# GMSL_DESERIALIZER.net
KiCad netlist of a schematic drawn in Altium Designer
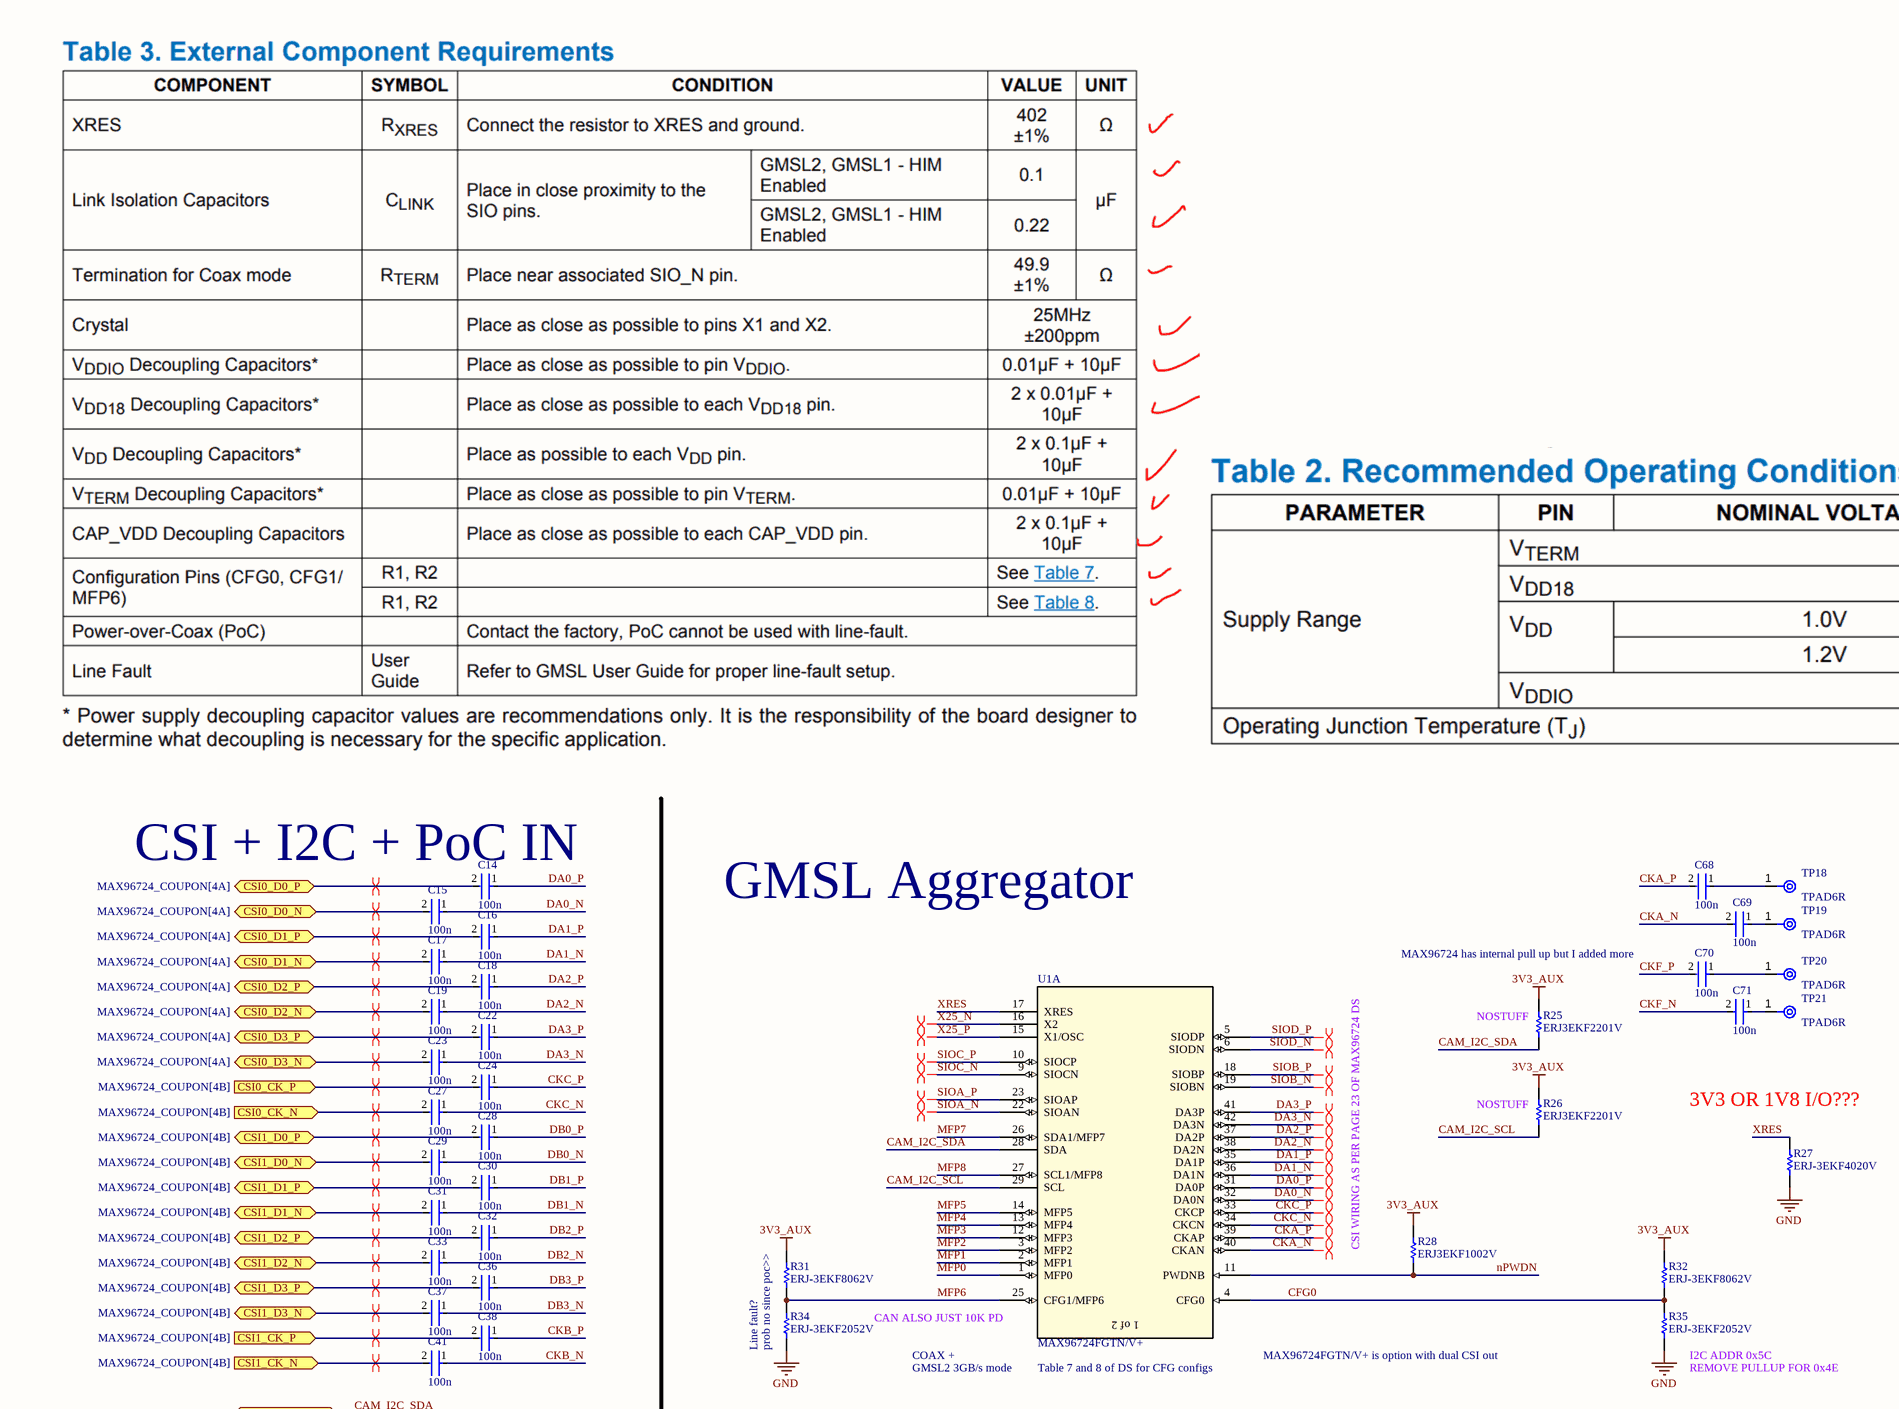
[diagram p0: GMSL_DESERIALIZER.SchDoc, top left]
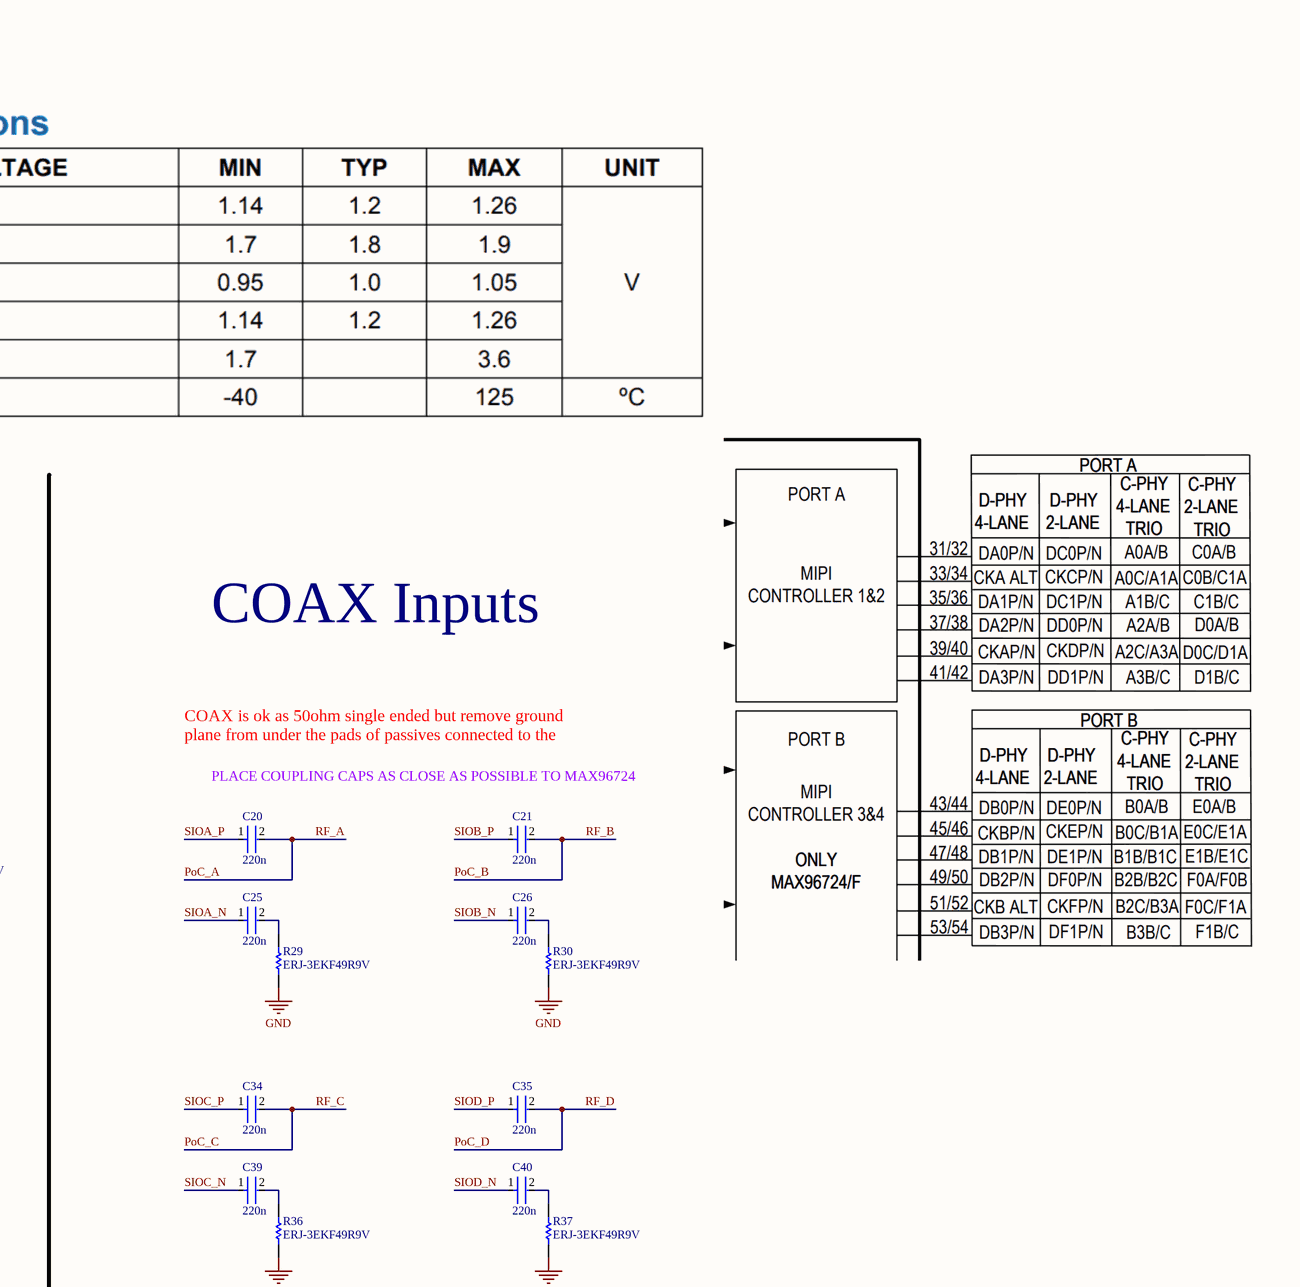
[diagram p1: GMSL_DESERIALIZER.SchDoc, top right]
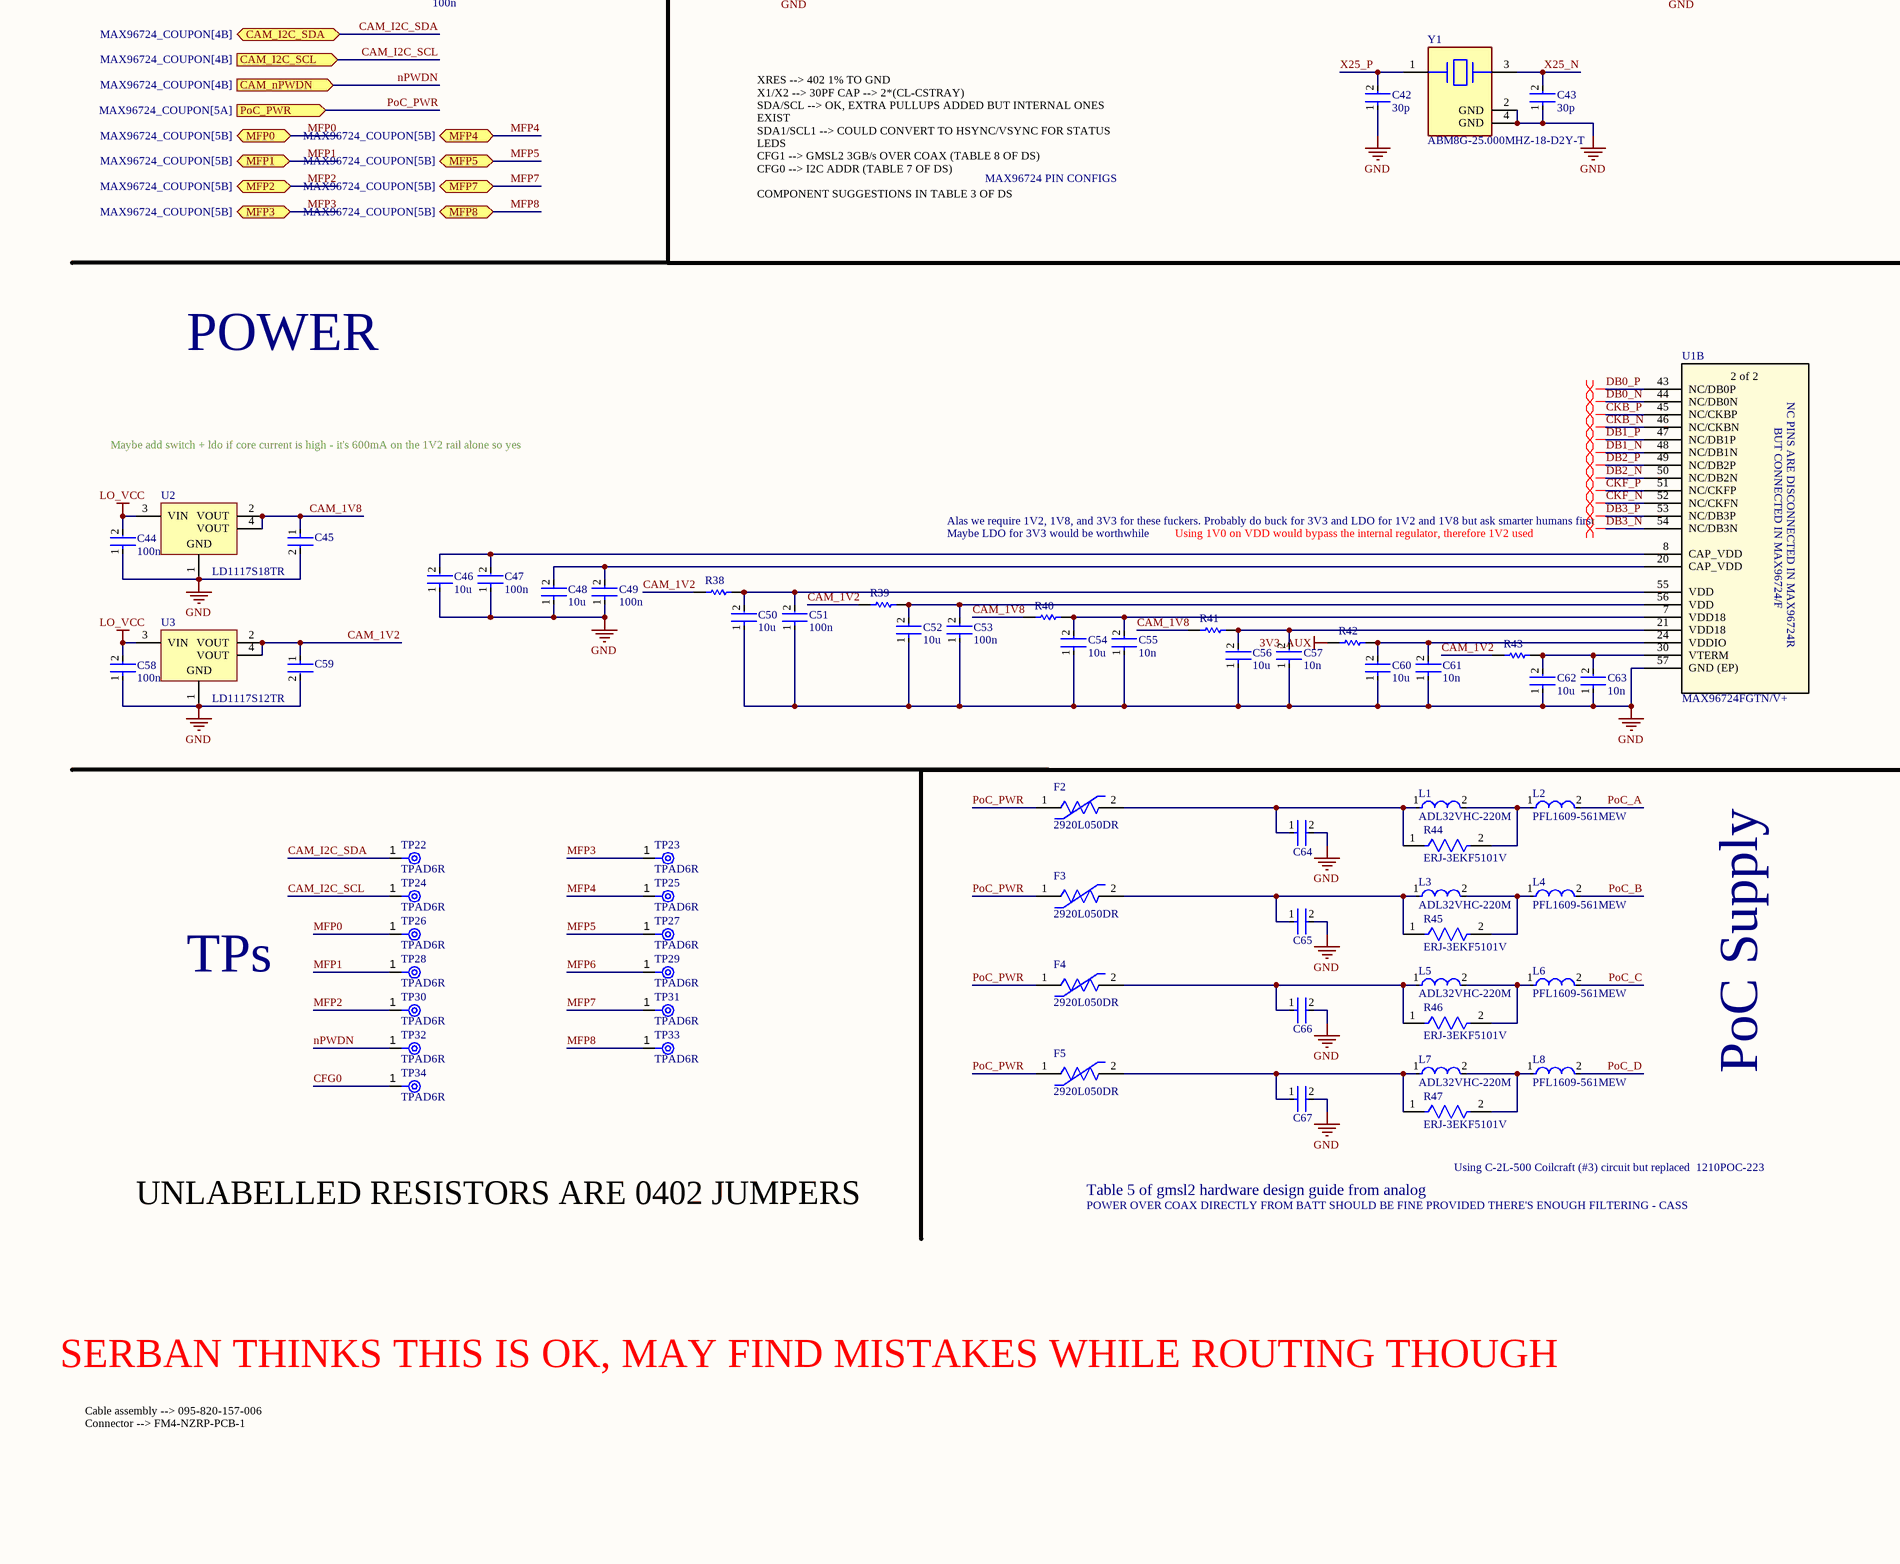
[diagram p2: GMSL_DESERIALIZER.SchDoc, bottom left]
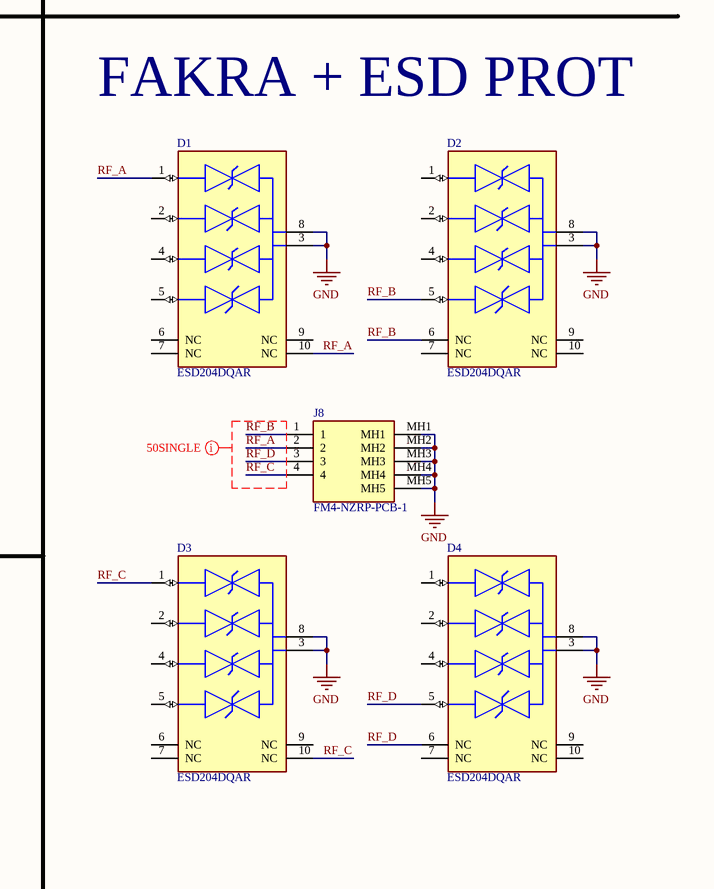
[diagram p3: GMSL_DESERIALIZER.SchDoc, bottom right]

(export (version "E")
  (design (tool "Eeschema 10.0.6"))
  (components
    (comp (ref "C14")
      (value "100n")
      (footprint "FP-0402-L_1_0_0_05-W_0_5-IPC_A")
      (description "LARGE PADS, 0402 CAP, CHANGE COMMENT TO MATCH REAL P/N")
      (libsource (lib "Space Concordia") (part "b4654b650e69147ec39a6b967a45e02"))
    )
    (comp (ref "C15")
      (value "100n")
      (footprint "FP-0402-L_1_0_0_05-W_0_5-IPC_A")
      (description "LARGE PADS, 0402 CAP, CHANGE COMMENT TO MATCH REAL P/N")
      (libsource (lib "Space Concordia") (part "b4654b650e69147ec39a6b967a45e02"))
    )
    (comp (ref "C16")
      (value "100n")
      (footprint "FP-0402-L_1_0_0_05-W_0_5-IPC_A")
      (description "LARGE PADS, 0402 CAP, CHANGE COMMENT TO MATCH REAL P/N")
      (libsource (lib "Space Concordia") (part "b4654b650e69147ec39a6b967a45e02"))
    )
    (comp (ref "C17")
      (value "100n")
      (footprint "FP-0402-L_1_0_0_05-W_0_5-IPC_A")
      (description "LARGE PADS, 0402 CAP, CHANGE COMMENT TO MATCH REAL P/N")
      (libsource (lib "Space Concordia") (part "b4654b650e69147ec39a6b967a45e02"))
    )
    (comp (ref "C18")
      (value "100n")
      (footprint "FP-0402-L_1_0_0_05-W_0_5-IPC_A")
      (description "LARGE PADS, 0402 CAP, CHANGE COMMENT TO MATCH REAL P/N")
      (libsource (lib "Space Concordia") (part "b4654b650e69147ec39a6b967a45e02"))
    )
    (comp (ref "C19")
      (value "100n")
      (footprint "FP-0402-L_1_0_0_05-W_0_5-IPC_A")
      (description "LARGE PADS, 0402 CAP, CHANGE COMMENT TO MATCH REAL P/N")
      (libsource (lib "Space Concordia") (part "b4654b650e69147ec39a6b967a45e02"))
    )
    (comp (ref "C20")
      (value "220n")
      (footprint "FP-0402-L_1_0_0_05-W_0_5-IPC_A")
      (description "LARGE PADS, 0402 CAP, CHANGE COMMENT TO MATCH REAL P/N")
      (libsource (lib "Space Concordia") (part "b4654b650e69147ec39a6b967a45e02"))
    )
    (comp (ref "C21")
      (value "220n")
      (footprint "FP-0402-L_1_0_0_05-W_0_5-IPC_A")
      (description "LARGE PADS, 0402 CAP, CHANGE COMMENT TO MATCH REAL P/N")
      (libsource (lib "Space Concordia") (part "b4654b650e69147ec39a6b967a45e02"))
    )
    (comp (ref "C22")
      (value "100n")
      (footprint "FP-0402-L_1_0_0_05-W_0_5-IPC_A")
      (description "LARGE PADS, 0402 CAP, CHANGE COMMENT TO MATCH REAL P/N")
      (libsource (lib "Space Concordia") (part "b4654b650e69147ec39a6b967a45e02"))
    )
    (comp (ref "C23")
      (value "100n")
      (footprint "FP-0402-L_1_0_0_05-W_0_5-IPC_A")
      (description "LARGE PADS, 0402 CAP, CHANGE COMMENT TO MATCH REAL P/N")
      (libsource (lib "Space Concordia") (part "b4654b650e69147ec39a6b967a45e02"))
    )
    (comp (ref "C24")
      (value "100n")
      (footprint "FP-0402-L_1_0_0_05-W_0_5-IPC_A")
      (description "LARGE PADS, 0402 CAP, CHANGE COMMENT TO MATCH REAL P/N")
      (libsource (lib "Space Concordia") (part "b4654b650e69147ec39a6b967a45e02"))
    )
    (comp (ref "C25")
      (value "220n")
      (footprint "FP-0402-L_1_0_0_05-W_0_5-IPC_A")
      (description "LARGE PADS, 0402 CAP, CHANGE COMMENT TO MATCH REAL P/N")
      (libsource (lib "Space Concordia") (part "b4654b650e69147ec39a6b967a45e02"))
    )
    (comp (ref "C26")
      (value "220n")
      (footprint "FP-0402-L_1_0_0_05-W_0_5-IPC_A")
      (description "LARGE PADS, 0402 CAP, CHANGE COMMENT TO MATCH REAL P/N")
      (libsource (lib "Space Concordia") (part "b4654b650e69147ec39a6b967a45e02"))
    )
    (comp (ref "C27")
      (value "100n")
      (footprint "FP-0402-L_1_0_0_05-W_0_5-IPC_A")
      (description "LARGE PADS, 0402 CAP, CHANGE COMMENT TO MATCH REAL P/N")
      (libsource (lib "Space Concordia") (part "b4654b650e69147ec39a6b967a45e02"))
    )
    (comp (ref "C28")
      (value "100n")
      (footprint "FP-0402-L_1_0_0_05-W_0_5-IPC_A")
      (description "LARGE PADS, 0402 CAP, CHANGE COMMENT TO MATCH REAL P/N")
      (libsource (lib "Space Concordia") (part "b4654b650e69147ec39a6b967a45e02"))
    )
    (comp (ref "C29")
      (value "100n")
      (footprint "FP-0402-L_1_0_0_05-W_0_5-IPC_A")
      (description "LARGE PADS, 0402 CAP, CHANGE COMMENT TO MATCH REAL P/N")
      (libsource (lib "Space Concordia") (part "b4654b650e69147ec39a6b967a45e02"))
    )
    (comp (ref "C30")
      (value "100n")
      (footprint "FP-0402-L_1_0_0_05-W_0_5-IPC_A")
      (description "LARGE PADS, 0402 CAP, CHANGE COMMENT TO MATCH REAL P/N")
      (libsource (lib "Space Concordia") (part "b4654b650e69147ec39a6b967a45e02"))
    )
    (comp (ref "C31")
      (value "100n")
      (footprint "FP-0402-L_1_0_0_05-W_0_5-IPC_A")
      (description "LARGE PADS, 0402 CAP, CHANGE COMMENT TO MATCH REAL P/N")
      (libsource (lib "Space Concordia") (part "b4654b650e69147ec39a6b967a45e02"))
    )
    (comp (ref "C32")
      (value "100n")
      (footprint "FP-0402-L_1_0_0_05-W_0_5-IPC_A")
      (description "LARGE PADS, 0402 CAP, CHANGE COMMENT TO MATCH REAL P/N")
      (libsource (lib "Space Concordia") (part "b4654b650e69147ec39a6b967a45e02"))
    )
    (comp (ref "C33")
      (value "100n")
      (footprint "FP-0402-L_1_0_0_05-W_0_5-IPC_A")
      (description "LARGE PADS, 0402 CAP, CHANGE COMMENT TO MATCH REAL P/N")
      (libsource (lib "Space Concordia") (part "b4654b650e69147ec39a6b967a45e02"))
    )
    (comp (ref "C34")
      (value "220n")
      (footprint "FP-0402-L_1_0_0_05-W_0_5-IPC_A")
      (description "LARGE PADS, 0402 CAP, CHANGE COMMENT TO MATCH REAL P/N")
      (libsource (lib "Space Concordia") (part "b4654b650e69147ec39a6b967a45e02"))
    )
    (comp (ref "C35")
      (value "220n")
      (footprint "FP-0402-L_1_0_0_05-W_0_5-IPC_A")
      (description "LARGE PADS, 0402 CAP, CHANGE COMMENT TO MATCH REAL P/N")
      (libsource (lib "Space Concordia") (part "b4654b650e69147ec39a6b967a45e02"))
    )
    (comp (ref "C36")
      (value "100n")
      (footprint "FP-0402-L_1_0_0_05-W_0_5-IPC_A")
      (description "LARGE PADS, 0402 CAP, CHANGE COMMENT TO MATCH REAL P/N")
      (libsource (lib "Space Concordia") (part "b4654b650e69147ec39a6b967a45e02"))
    )
    (comp (ref "C37")
      (value "100n")
      (footprint "FP-0402-L_1_0_0_05-W_0_5-IPC_A")
      (description "LARGE PADS, 0402 CAP, CHANGE COMMENT TO MATCH REAL P/N")
      (libsource (lib "Space Concordia") (part "b4654b650e69147ec39a6b967a45e02"))
    )
    (comp (ref "C38")
      (value "100n")
      (footprint "FP-0402-L_1_0_0_05-W_0_5-IPC_A")
      (description "LARGE PADS, 0402 CAP, CHANGE COMMENT TO MATCH REAL P/N")
      (libsource (lib "Space Concordia") (part "b4654b650e69147ec39a6b967a45e02"))
    )
    (comp (ref "C39")
      (value "220n")
      (footprint "FP-0402-L_1_0_0_05-W_0_5-IPC_A")
      (description "LARGE PADS, 0402 CAP, CHANGE COMMENT TO MATCH REAL P/N")
      (libsource (lib "Space Concordia") (part "b4654b650e69147ec39a6b967a45e02"))
    )
    (comp (ref "C40")
      (value "220n")
      (footprint "FP-0402-L_1_0_0_05-W_0_5-IPC_A")
      (description "LARGE PADS, 0402 CAP, CHANGE COMMENT TO MATCH REAL P/N")
      (libsource (lib "Space Concordia") (part "b4654b650e69147ec39a6b967a45e02"))
    )
    (comp (ref "C41")
      (value "100n")
      (footprint "FP-0402-L_1_0_0_05-W_0_5-IPC_A")
      (description "LARGE PADS, 0402 CAP, CHANGE COMMENT TO MATCH REAL P/N")
      (libsource (lib "Space Concordia") (part "b4654b650e69147ec39a6b967a45e02"))
    )
    (comp (ref "C42")
      (value "30p")
      (footprint "FP-0402-L_1_0_0_05-W_0_5-IPC_A")
      (description "LARGE PADS, 0402 CAP, CHANGE COMMENT TO MATCH REAL P/N")
      (libsource (lib "Space Concordia") (part "b4654b650e69147ec39a6b967a45e02"))
    )
    (comp (ref "C43")
      (value "30p")
      (footprint "FP-0402-L_1_0_0_05-W_0_5-IPC_A")
      (description "LARGE PADS, 0402 CAP, CHANGE COMMENT TO MATCH REAL P/N")
      (libsource (lib "Space Concordia") (part "b4654b650e69147ec39a6b967a45e02"))
    )
    (comp (ref "C44")
      (value "100n")
      (footprint "FP-0402-L_1_0_0_05-W_0_5-IPC_A")
      (description "LARGE PADS, 0402 CAP, CHANGE COMMENT TO MATCH REAL P/N")
      (libsource (lib "Space Concordia") (part "b4654b650e69147ec39a6b967a45e02"))
    )
    (comp (ref "C45")
      (value "GRM188R60J106ME47D")
      (footprint "FP-GRM188-0_1-e0_2_0_55-IPC_A")
      (description "Chip Multilayer Ceramic Capacitors for General Purpose, 0603, 10uF, X5R, 15%, 20%, 6.3V")
      (fields (field (name "VOLTAGE") "6.3V") (field (name "TOLERANCE") "20%"))
      (libsource (lib "Altium Content Vault") (part "02cd4be3c70576c341d710602a673aa"))
    )
    (comp (ref "C46")
      (value "10u")
      (footprint "FP-0402-L_1_0_0_05-W_0_5-IPC_A")
      (description "LARGE PADS, 0402 CAP, CHANGE COMMENT TO MATCH REAL P/N")
      (libsource (lib "Space Concordia") (part "b4654b650e69147ec39a6b967a45e02"))
    )
    (comp (ref "C47")
      (value "100n")
      (footprint "FP-0402-L_1_0_0_05-W_0_5-IPC_A")
      (description "LARGE PADS, 0402 CAP, CHANGE COMMENT TO MATCH REAL P/N")
      (libsource (lib "Space Concordia") (part "b4654b650e69147ec39a6b967a45e02"))
    )
    (comp (ref "C48")
      (value "10u")
      (footprint "FP-0402-L_1_0_0_05-W_0_5-IPC_A")
      (description "LARGE PADS, 0402 CAP, CHANGE COMMENT TO MATCH REAL P/N")
      (libsource (lib "Space Concordia") (part "b4654b650e69147ec39a6b967a45e02"))
    )
    (comp (ref "C49")
      (value "100n")
      (footprint "FP-0402-L_1_0_0_05-W_0_5-IPC_A")
      (description "LARGE PADS, 0402 CAP, CHANGE COMMENT TO MATCH REAL P/N")
      (libsource (lib "Space Concordia") (part "b4654b650e69147ec39a6b967a45e02"))
    )
    (comp (ref "C50")
      (value "10u")
      (footprint "FP-0402-L_1_0_0_05-W_0_5-IPC_A")
      (description "LARGE PADS, 0402 CAP, CHANGE COMMENT TO MATCH REAL P/N")
      (libsource (lib "Space Concordia") (part "b4654b650e69147ec39a6b967a45e02"))
    )
    (comp (ref "C51")
      (value "100n")
      (footprint "FP-0402-L_1_0_0_05-W_0_5-IPC_A")
      (description "LARGE PADS, 0402 CAP, CHANGE COMMENT TO MATCH REAL P/N")
      (libsource (lib "Space Concordia") (part "b4654b650e69147ec39a6b967a45e02"))
    )
    (comp (ref "C52")
      (value "10u")
      (footprint "FP-0402-L_1_0_0_05-W_0_5-IPC_A")
      (description "LARGE PADS, 0402 CAP, CHANGE COMMENT TO MATCH REAL P/N")
      (libsource (lib "Space Concordia") (part "b4654b650e69147ec39a6b967a45e02"))
    )
    (comp (ref "C53")
      (value "100n")
      (footprint "FP-0402-L_1_0_0_05-W_0_5-IPC_A")
      (description "LARGE PADS, 0402 CAP, CHANGE COMMENT TO MATCH REAL P/N")
      (libsource (lib "Space Concordia") (part "b4654b650e69147ec39a6b967a45e02"))
    )
    (comp (ref "C54")
      (value "10u")
      (footprint "FP-0402-L_1_0_0_05-W_0_5-IPC_A")
      (description "LARGE PADS, 0402 CAP, CHANGE COMMENT TO MATCH REAL P/N")
      (libsource (lib "Space Concordia") (part "b4654b650e69147ec39a6b967a45e02"))
    )
    (comp (ref "C55")
      (value "10n")
      (footprint "FP-0402-L_1_0_0_05-W_0_5-IPC_A")
      (description "LARGE PADS, 0402 CAP, CHANGE COMMENT TO MATCH REAL P/N")
      (libsource (lib "Space Concordia") (part "b4654b650e69147ec39a6b967a45e02"))
    )
    (comp (ref "C56")
      (value "10u")
      (footprint "FP-0402-L_1_0_0_05-W_0_5-IPC_A")
      (description "LARGE PADS, 0402 CAP, CHANGE COMMENT TO MATCH REAL P/N")
      (libsource (lib "Space Concordia") (part "b4654b650e69147ec39a6b967a45e02"))
    )
    (comp (ref "C57")
      (value "10n")
      (footprint "FP-0402-L_1_0_0_05-W_0_5-IPC_A")
      (description "LARGE PADS, 0402 CAP, CHANGE COMMENT TO MATCH REAL P/N")
      (libsource (lib "Space Concordia") (part "b4654b650e69147ec39a6b967a45e02"))
    )
    (comp (ref "C58")
      (value "100n")
      (footprint "FP-0402-L_1_0_0_05-W_0_5-IPC_A")
      (description "LARGE PADS, 0402 CAP, CHANGE COMMENT TO MATCH REAL P/N")
      (libsource (lib "Space Concordia") (part "b4654b650e69147ec39a6b967a45e02"))
    )
    (comp (ref "C59")
      (value "GRM188R60J106ME47D")
      (footprint "FP-GRM188-0_1-e0_2_0_55-IPC_A")
      (description "Chip Multilayer Ceramic Capacitors for General Purpose, 0603, 10uF, X5R, 15%, 20%, 6.3V")
      (fields (field (name "VOLTAGE") "6.3V") (field (name "TOLERANCE") "20%"))
      (libsource (lib "Altium Content Vault") (part "02cd4be3c70576c341d710602a673aa"))
    )
    (comp (ref "C60")
      (value "10u")
      (footprint "FP-0402-L_1_0_0_05-W_0_5-IPC_A")
      (description "LARGE PADS, 0402 CAP, CHANGE COMMENT TO MATCH REAL P/N")
      (libsource (lib "Space Concordia") (part "b4654b650e69147ec39a6b967a45e02"))
    )
    (comp (ref "C61")
      (value "10n")
      (footprint "FP-0402-L_1_0_0_05-W_0_5-IPC_A")
      (description "LARGE PADS, 0402 CAP, CHANGE COMMENT TO MATCH REAL P/N")
      (libsource (lib "Space Concordia") (part "b4654b650e69147ec39a6b967a45e02"))
    )
    (comp (ref "C62")
      (value "10u")
      (footprint "FP-0402-L_1_0_0_05-W_0_5-IPC_A")
      (description "LARGE PADS, 0402 CAP, CHANGE COMMENT TO MATCH REAL P/N")
      (libsource (lib "Space Concordia") (part "b4654b650e69147ec39a6b967a45e02"))
    )
    (comp (ref "C63")
      (value "10n")
      (footprint "FP-0402-L_1_0_0_05-W_0_5-IPC_A")
      (description "LARGE PADS, 0402 CAP, CHANGE COMMENT TO MATCH REAL P/N")
      (libsource (lib "Space Concordia") (part "b4654b650e69147ec39a6b967a45e02"))
    )
    (comp (ref "C64")
      (value "GRM21BR61E226ME44L")
      (footprint "FP-GRM21B-0_2-e0_2_0_7-IPC_B")
      (description "Chip Multilayer Ceramic Capacitors for General Purpose, 0805, 22uF, X5R, 15%, 20%, 25V")
      (fields (field (name "TOLERANCE") "20%") (field (name "VOLTAGE") "25V"))
      (libsource (lib "Altium Content Vault") (part "b4654b650e69147ec39a6b967a45e02"))
    )
    (comp (ref "C65")
      (value "GRM21BR61E226ME44L")
      (footprint "FP-GRM21B-0_2-e0_2_0_7-IPC_B")
      (description "Chip Multilayer Ceramic Capacitors for General Purpose, 0805, 22uF, X5R, 15%, 20%, 25V")
      (fields (field (name "TOLERANCE") "20%") (field (name "VOLTAGE") "25V"))
      (libsource (lib "Altium Content Vault") (part "b4654b650e69147ec39a6b967a45e02"))
    )
    (comp (ref "C66")
      (value "GRM21BR61E226ME44L")
      (footprint "FP-GRM21B-0_2-e0_2_0_7-IPC_B")
      (description "Chip Multilayer Ceramic Capacitors for General Purpose, 0805, 22uF, X5R, 15%, 20%, 25V")
      (fields (field (name "TOLERANCE") "20%") (field (name "VOLTAGE") "25V"))
      (libsource (lib "Altium Content Vault") (part "b4654b650e69147ec39a6b967a45e02"))
    )
    (comp (ref "C67")
      (value "GRM21BR61E226ME44L")
      (footprint "FP-GRM21B-0_2-e0_2_0_7-IPC_B")
      (description "Chip Multilayer Ceramic Capacitors for General Purpose, 0805, 22uF, X5R, 15%, 20%, 25V")
      (fields (field (name "TOLERANCE") "20%") (field (name "VOLTAGE") "25V"))
      (libsource (lib "Altium Content Vault") (part "b4654b650e69147ec39a6b967a45e02"))
    )
    (comp (ref "C68")
      (value "100n")
      (footprint "FP-0402-L_1_0_0_05-W_0_5-IPC_A")
      (description "LARGE PADS, 0402 CAP, CHANGE COMMENT TO MATCH REAL P/N")
      (libsource (lib "Space Concordia") (part "b4654b650e69147ec39a6b967a45e02"))
    )
    (comp (ref "C69")
      (value "100n")
      (footprint "FP-0402-L_1_0_0_05-W_0_5-IPC_A")
      (description "LARGE PADS, 0402 CAP, CHANGE COMMENT TO MATCH REAL P/N")
      (libsource (lib "Space Concordia") (part "b4654b650e69147ec39a6b967a45e02"))
    )
    (comp (ref "C70")
      (value "100n")
      (footprint "FP-0402-L_1_0_0_05-W_0_5-IPC_A")
      (description "LARGE PADS, 0402 CAP, CHANGE COMMENT TO MATCH REAL P/N")
      (libsource (lib "Space Concordia") (part "b4654b650e69147ec39a6b967a45e02"))
    )
    (comp (ref "C71")
      (value "100n")
      (footprint "FP-0402-L_1_0_0_05-W_0_5-IPC_A")
      (description "LARGE PADS, 0402 CAP, CHANGE COMMENT TO MATCH REAL P/N")
      (libsource (lib "Space Concordia") (part "b4654b650e69147ec39a6b967a45e02"))
    )
    (comp (ref "D1")
      (value "ESD204DQAR")
      (footprint "FP-DQA0010A-MFG")
      (description "4-CHANNEL LOW-CAPACITANCE SURGE")
      (fields
        (field (name "MANUFACTURER") "Texas Instruments")
        (field (name "OCTOPART") "https://octopart.com/esd204dqar-texas+instruments-89917476")
      )
      (libsource (lib "Altium Content Vault") (part "1465e58c1818c7767b55926832f0bf5"))
    )
    (comp (ref "D2")
      (value "ESD204DQAR")
      (footprint "FP-DQA0010A-MFG")
      (description "4-CHANNEL LOW-CAPACITANCE SURGE")
      (fields
        (field (name "MANUFACTURER") "Texas Instruments")
        (field (name "OCTOPART") "https://octopart.com/esd204dqar-texas+instruments-89917476")
      )
      (libsource (lib "Altium Content Vault") (part "1465e58c1818c7767b55926832f0bf5"))
    )
    (comp (ref "D3")
      (value "ESD204DQAR")
      (footprint "FP-DQA0010A-MFG")
      (description "4-CHANNEL LOW-CAPACITANCE SURGE")
      (fields
        (field (name "MANUFACTURER") "Texas Instruments")
        (field (name "OCTOPART") "https://octopart.com/esd204dqar-texas+instruments-89917476")
      )
      (libsource (lib "Altium Content Vault") (part "1465e58c1818c7767b55926832f0bf5"))
    )
    (comp (ref "D4")
      (value "ESD204DQAR")
      (footprint "FP-DQA0010A-MFG")
      (description "4-CHANNEL LOW-CAPACITANCE SURGE")
      (fields
        (field (name "MANUFACTURER") "Texas Instruments")
        (field (name "OCTOPART") "https://octopart.com/esd204dqar-texas+instruments-89917476")
      )
      (libsource (lib "Altium Content Vault") (part "1465e58c1818c7767b55926832f0bf5"))
    )
    (comp (ref "F2")
      (value "2920L050DR")
      (footprint "FP-2920L050DR-MFG")
      (description "PTC RESET FUSE 60V 500MA 2920")
      (libsource (lib "Altium Content Vault") (part "1c6d77a0208143737455a0c7eb396be"))
    )
    (comp (ref "F3")
      (value "2920L050DR")
      (footprint "FP-2920L050DR-MFG")
      (description "PTC RESET FUSE 60V 500MA 2920")
      (libsource (lib "Altium Content Vault") (part "1c6d77a0208143737455a0c7eb396be"))
    )
    (comp (ref "F4")
      (value "2920L050DR")
      (footprint "FP-2920L050DR-MFG")
      (description "PTC RESET FUSE 60V 500MA 2920")
      (libsource (lib "Altium Content Vault") (part "1c6d77a0208143737455a0c7eb396be"))
    )
    (comp (ref "F5")
      (value "2920L050DR")
      (footprint "FP-2920L050DR-MFG")
      (description "PTC RESET FUSE 60V 500MA 2920")
      (libsource (lib "Altium Content Vault") (part "1c6d77a0208143737455a0c7eb396be"))
    )
    (comp (ref "J8")
      (value "FM4-NZRP-PCB-1")
      (footprint "FM4-NZRP-PCB-1-Footprint-1")
      (description "Connector RF Mini-FAKRA Plug 9GHz 50Ohm Solder Right Angle Through Hole")
      (libsource (lib "Space Concordia") (part "CMP-002-00085-1"))
    )
    (comp (ref "L1")
      (value "ADL32VHC-220M")
      (footprint "FP-1210POC-MFG")
      (description "NOT COILCRAFT - ACTUAL P# --> ADL32VHC-220M\r\n - Power Injection Chokes for PoC")
      (fields
        (field (name "MANUFACTURER") "coilcraft")
        (field (name "OCTOPART") "https://octopart.com/1210poc-223mrc-coilcraft-103207315")
      )
      (libsource (lib "Altium Content Vault") (part "725321dda6339637d4d059423bc1c3c"))
    )
    (comp (ref "L2")
      (value "PFL1609-561MEW")
      (footprint "FP-PFL1609-MFG")
      (description "Fixed Inductors PFL1609 Low Profile 0.56 uH 20 % 1.4 A")
      (fields (field (name "MANUFACTURER") "coilcraft") (field (name "TOLERANCE") "20%"))
      (libsource (lib "Altium Content Vault") (part "725321dda6339637d4d059423bc1c3c"))
    )
    (comp (ref "L3")
      (value "ADL32VHC-220M")
      (footprint "FP-1210POC-MFG")
      (description "NOT COILCRAFT - ACTUAL P# --> ADL32VHC-220M\r\n - Power Injection Chokes for PoC")
      (fields
        (field (name "MANUFACTURER") "coilcraft")
        (field (name "OCTOPART") "https://octopart.com/1210poc-223mrc-coilcraft-103207315")
      )
      (libsource (lib "Altium Content Vault") (part "725321dda6339637d4d059423bc1c3c"))
    )
    (comp (ref "L4")
      (value "PFL1609-561MEW")
      (footprint "FP-PFL1609-MFG")
      (description "Fixed Inductors PFL1609 Low Profile 0.56 uH 20 % 1.4 A")
      (fields (field (name "MANUFACTURER") "coilcraft") (field (name "TOLERANCE") "20%"))
      (libsource (lib "Altium Content Vault") (part "725321dda6339637d4d059423bc1c3c"))
    )
    (comp (ref "L5")
      (value "ADL32VHC-220M")
      (footprint "FP-1210POC-MFG")
      (description "NOT COILCRAFT - ACTUAL P# --> ADL32VHC-220M\r\n - Power Injection Chokes for PoC")
      (fields
        (field (name "MANUFACTURER") "coilcraft")
        (field (name "OCTOPART") "https://octopart.com/1210poc-223mrc-coilcraft-103207315")
      )
      (libsource (lib "Altium Content Vault") (part "725321dda6339637d4d059423bc1c3c"))
    )
    (comp (ref "L6")
      (value "PFL1609-561MEW")
      (footprint "FP-PFL1609-MFG")
      (description "Fixed Inductors PFL1609 Low Profile 0.56 uH 20 % 1.4 A")
      (fields (field (name "MANUFACTURER") "coilcraft") (field (name "TOLERANCE") "20%"))
      (libsource (lib "Altium Content Vault") (part "725321dda6339637d4d059423bc1c3c"))
    )
    (comp (ref "L7")
      (value "ADL32VHC-220M")
      (footprint "FP-1210POC-MFG")
      (description "NOT COILCRAFT - ACTUAL P# --> ADL32VHC-220M\r\n - Power Injection Chokes for PoC")
      (fields
        (field (name "MANUFACTURER") "coilcraft")
        (field (name "OCTOPART") "https://octopart.com/1210poc-223mrc-coilcraft-103207315")
      )
      (libsource (lib "Altium Content Vault") (part "725321dda6339637d4d059423bc1c3c"))
    )
    (comp (ref "L8")
      (value "PFL1609-561MEW")
      (footprint "FP-PFL1609-MFG")
      (description "Fixed Inductors PFL1609 Low Profile 0.56 uH 20 % 1.4 A")
      (fields (field (name "MANUFACTURER") "coilcraft") (field (name "TOLERANCE") "20%"))
      (libsource (lib "Altium Content Vault") (part "725321dda6339637d4d059423bc1c3c"))
    )
    (comp (ref "R25")
      (value "ERJ3EKF2201V")
      (footprint "RESC1608X55X30LL15T15")
      (fields (field (name "MANUFACTURER") "Panasonic"))
      (libsource (lib "Altium Content Vault") (part "RES"))
    )
    (comp (ref "R26")
      (value "ERJ3EKF2201V")
      (footprint "RESC1608X55X30LL15T15")
      (fields (field (name "MANUFACTURER") "Panasonic"))
      (libsource (lib "Altium Content Vault") (part "RES"))
    )
    (comp (ref "R27")
      (value "ERJ-3EKF4020V")
      (footprint "RESC1608X55X30LL15T15")
      (fields (field (name "MANUFACTURER") "Panasonic"))
      (libsource (lib "Altium Content Vault") (part "RES"))
    )
    (comp (ref "R28")
      (value "ERJ3EKF1002V")
      (footprint "RESC1609X55X30LL15T15")
      (description "Chip Resistor, 10 KOhm, +/- 1%, 0.1 W, -55 to 155 degC, 0603 (1608 Metric), RoHS, Tape and Reel")
      (fields (field (name "TOLERANCE") "1%") (field (name "MANUFACTURER") "Panasonic"))
      (libsource (lib "Altium Content Vault") (part "RES-2"))
    )
    (comp (ref "R29")
      (value "ERJ-3EKF49R9V")
      (footprint "RESC1608X55X30ML15T15")
      (fields (field (name "MANUFACTURER") "Panasonic"))
      (libsource (lib "Altium Content Vault") (part "RES"))
    )
    (comp (ref "R30")
      (value "ERJ-3EKF49R9V")
      (footprint "RESC1608X55X30ML15T15")
      (fields (field (name "MANUFACTURER") "Panasonic"))
      (libsource (lib "Altium Content Vault") (part "RES"))
    )
    (comp (ref "R31")
      (value "ERJ-3EKF8062V")
      (footprint "RESC1608X55X30LL15T15")
      (fields (field (name "MANUFACTURER") "Panasonic"))
      (libsource (lib "Altium Content Vault") (part "RES"))
    )
    (comp (ref "R32")
      (value "ERJ-3EKF8062V")
      (footprint "RESC1608X55X30LL15T15")
      (fields (field (name "MANUFACTURER") "Panasonic"))
      (libsource (lib "Altium Content Vault") (part "RES"))
    )
    (comp (ref "R34")
      (value "ERJ-3EKF2052V")
      (footprint "RESC1608X55X30NL15T15")
      (fields (field (name "MANUFACTURER") "Panasonic"))
      (libsource (lib "Altium Content Vault") (part "RES"))
    )
    (comp (ref "R35")
      (value "ERJ-3EKF2052V")
      (footprint "RESC1608X55X30NL15T15")
      (fields (field (name "MANUFACTURER") "Panasonic"))
      (libsource (lib "Altium Content Vault") (part "RES"))
    )
    (comp (ref "R36")
      (value "ERJ-3EKF49R9V")
      (footprint "RESC1608X55X30ML15T15")
      (fields (field (name "MANUFACTURER") "Panasonic"))
      (libsource (lib "Altium Content Vault") (part "RES"))
    )
    (comp (ref "R37")
      (value "ERJ-3EKF49R9V")
      (footprint "RESC1608X55X30ML15T15")
      (fields (field (name "MANUFACTURER") "Panasonic"))
      (libsource (lib "Altium Content Vault") (part "RES"))
    )
    (comp (ref "R38")
      (value "RC0402JR-070RL")
      (footprint "RESC1005X40X25NL05T10")
      (fields (field (name "MANUFACTURER") "Yageo / Phycomp"))
      (libsource (lib "Altium Content Vault") (part "RES"))
    )
    (comp (ref "R39")
      (value "RC0402JR-070RL")
      (footprint "RESC1005X40X25NL05T10")
      (fields (field (name "MANUFACTURER") "Yageo / Phycomp"))
      (libsource (lib "Altium Content Vault") (part "RES"))
    )
    (comp (ref "R40")
      (value "RC0402JR-070RL")
      (footprint "RESC1005X40X25NL05T10")
      (fields (field (name "MANUFACTURER") "Yageo / Phycomp"))
      (libsource (lib "Altium Content Vault") (part "RES"))
    )
    (comp (ref "R41")
      (value "RC0402JR-070RL")
      (footprint "RESC1005X40X25NL05T10")
      (fields (field (name "MANUFACTURER") "Yageo / Phycomp"))
      (libsource (lib "Altium Content Vault") (part "RES"))
    )
    (comp (ref "R42")
      (value "RC0402JR-070RL")
      (footprint "RESC1005X40X25NL05T10")
      (fields (field (name "MANUFACTURER") "Yageo / Phycomp"))
      (libsource (lib "Altium Content Vault") (part "RES"))
    )
    (comp (ref "R43")
      (value "RC0402JR-070RL")
      (footprint "RESC1005X40X25NL05T10")
      (fields (field (name "MANUFACTURER") "Yageo / Phycomp"))
      (libsource (lib "Altium Content Vault") (part "RES"))
    )
    (comp (ref "R44")
      (value "ERJ-3EKF5101V")
      (footprint "FP-ERJ3EK-MFG")
      (description "RES SMD 5.1K OHM 1% 1/10W 0603")
      (fields (field (name "TOLERANCE") "1%"))
      (libsource (lib "Altium Content Vault") (part "1029c3af85768c4190bb7ad29bc67b5"))
    )
    (comp (ref "R45")
      (value "ERJ-3EKF5101V")
      (footprint "FP-ERJ3EK-MFG")
      (description "RES SMD 5.1K OHM 1% 1/10W 0603")
      (fields (field (name "TOLERANCE") "1%"))
      (libsource (lib "Altium Content Vault") (part "1029c3af85768c4190bb7ad29bc67b5"))
    )
    (comp (ref "R46")
      (value "ERJ-3EKF5101V")
      (footprint "FP-ERJ3EK-MFG")
      (description "RES SMD 5.1K OHM 1% 1/10W 0603")
      (fields (field (name "TOLERANCE") "1%"))
      (libsource (lib "Altium Content Vault") (part "1029c3af85768c4190bb7ad29bc67b5"))
    )
    (comp (ref "R47")
      (value "ERJ-3EKF5101V")
      (footprint "FP-ERJ3EK-MFG")
      (description "RES SMD 5.1K OHM 1% 1/10W 0603")
      (fields (field (name "TOLERANCE") "1%"))
      (libsource (lib "Altium Content Vault") (part "1029c3af85768c4190bb7ad29bc67b5"))
    )
    (comp (ref "TP18")
      (value "TPAD6R")
      (footprint "New footprint 1")
      (description "Test Point .6mm")
      (libsource (lib "Space Concordia") (part "TP"))
    )
    (comp (ref "TP19")
      (value "TPAD6R")
      (footprint "New footprint 1")
      (description "Test Point .6mm")
      (libsource (lib "Space Concordia") (part "TP"))
    )
    (comp (ref "TP20")
      (value "TPAD6R")
      (footprint "New footprint 1")
      (description "Test Point .6mm")
      (libsource (lib "Space Concordia") (part "TP"))
    )
    (comp (ref "TP21")
      (value "TPAD6R")
      (footprint "New footprint 1")
      (description "Test Point .6mm")
      (libsource (lib "Space Concordia") (part "TP"))
    )
    (comp (ref "TP22")
      (value "TPAD6R")
      (footprint "New footprint 1")
      (description "Test Point .6mm")
      (libsource (lib "Space Concordia") (part "TP"))
    )
    (comp (ref "TP23")
      (value "TPAD6R")
      (footprint "New footprint 1")
      (description "Test Point .6mm")
      (libsource (lib "Space Concordia") (part "TP"))
    )
    (comp (ref "TP24")
      (value "TPAD6R")
      (footprint "New footprint 1")
      (description "Test Point .6mm")
      (libsource (lib "Space Concordia") (part "TP"))
    )
    (comp (ref "TP25")
      (value "TPAD6R")
      (footprint "New footprint 1")
      (description "Test Point .6mm")
      (libsource (lib "Space Concordia") (part "TP"))
    )
    (comp (ref "TP26")
      (value "TPAD6R")
      (footprint "New footprint 1")
      (description "Test Point .6mm")
      (libsource (lib "Space Concordia") (part "TP"))
    )
    (comp (ref "TP27")
      (value "TPAD6R")
      (footprint "New footprint 1")
      (description "Test Point .6mm")
      (libsource (lib "Space Concordia") (part "TP"))
    )
    (comp (ref "TP28")
      (value "TPAD6R")
      (footprint "New footprint 1")
      (description "Test Point .6mm")
      (libsource (lib "Space Concordia") (part "TP"))
    )
    (comp (ref "TP29")
      (value "TPAD6R")
      (footprint "New footprint 1")
      (description "Test Point .6mm")
      (libsource (lib "Space Concordia") (part "TP"))
    )
    (comp (ref "TP30")
      (value "TPAD6R")
      (footprint "New footprint 1")
      (description "Test Point .6mm")
      (libsource (lib "Space Concordia") (part "TP"))
    )
    (comp (ref "TP31")
      (value "TPAD6R")
      (footprint "New footprint 1")
      (description "Test Point .6mm")
      (libsource (lib "Space Concordia") (part "TP"))
    )
    (comp (ref "TP32")
      (value "TPAD6R")
      (footprint "New footprint 1")
      (description "Test Point .6mm")
      (libsource (lib "Space Concordia") (part "TP"))
    )
    (comp (ref "TP33")
      (value "TPAD6R")
      (footprint "New footprint 1")
      (description "Test Point .6mm")
      (libsource (lib "Space Concordia") (part "TP"))
    )
    (comp (ref "TP34")
      (value "TPAD6R")
      (footprint "New footprint 1")
      (description "Test Point .6mm")
      (libsource (lib "Space Concordia") (part "TP"))
    )
    (comp (ref "U1")
      (value "MAX96724FGTN/V+")
      (footprint "MAX96724FGTN_V+-Footprint-1")
      (description "Quad Tunneling GMSL2/1 to CSI-2 Deserializer")
      (libsource (lib "Space Concordia") (part "MAX96724FGTN_V+-Symbol-1"))
    )
    (comp (ref "U2")
      (value "LD1117S18TR")
      (footprint "SOT-223_M")
      (description "Fixed Low Drop Positive Voltage Regulator, 1.8V, 4-Pin SOT-223, Tape and Reel")
      (libsource (lib "Altium Content Vault") (part "PM-REG-LD1117-SOT4"))
    )
    (comp (ref "U3")
      (value "LD1117S12TR")
      (footprint "SOT-223_M")
      (description "Fixed Low Drop Positive Voltage Regulator, 1.2V, 4-Pin SOT-223, Tape and Reel")
      (libsource (lib "Altium Content Vault") (part "PM-REG-LD1117-SOT4"))
    )
    (comp (ref "Y1")
      (value "ABM8G-25.000MHZ-18-D2Y-T")
      (footprint "FP-ABM8G-MFG")
      (description "Crystal 25MHz ±20ppm (Tol) ±30ppm (Stability) 18pF FUND 60Ω 4-Pin SMD T/R")
      (fields (field (name "TOLERANCE") "20ppm"))
      (libsource (lib "Altium Content Vault") (part "48e526d86b7f2615d98721063c72f49"))
    )
  )
  (nets
    (net (code "1") (name "/CAM_1V2") (class "Default")
      (node (ref "C59") (pin "1") (pinfunction "1_1") (pintype "passive"))
      (node (ref "R38") (pin "1") (pinfunction "1_1") (pintype "passive"))
      (node (ref "R39") (pin "1") (pinfunction "1_1") (pintype "passive"))
      (node (ref "R43") (pin "1") (pinfunction "1_1") (pintype "passive"))
      (node (ref "U3") (pin "2") (pinfunction "VOUT_2") (pintype "power_in"))
      (node (ref "U3") (pin "4") (pinfunction "VOUT_4") (pintype "power_in"))
    )
    (net (code "2") (name "/CAM_1V8") (class "Default")
      (node (ref "C45") (pin "1") (pinfunction "1_1") (pintype "passive"))
      (node (ref "R40") (pin "1") (pinfunction "1_1") (pintype "passive"))
      (node (ref "R41") (pin "1") (pinfunction "1_1") (pintype "passive"))
      (node (ref "U2") (pin "2") (pinfunction "VOUT_2") (pintype "power_in"))
      (node (ref "U2") (pin "4") (pinfunction "VOUT_4") (pintype "power_in"))
    )
    (net (code "3") (name "/CAM_I2C_SCL") (class "Default")
      (node (ref "R26") (pin "1") (pinfunction "1_1") (pintype "passive"))
      (node (ref "TP24") (pin "1") (pinfunction "TP_1") (pintype "passive"))
      (node (ref "U1") (pin "29") (pinfunction "SCL_29") (pintype "passive"))
    )
    (net (code "4") (name "/CAM_I2C_SDA") (class "Default")
      (node (ref "R25") (pin "1") (pinfunction "1_1") (pintype "passive"))
      (node (ref "TP22") (pin "1") (pinfunction "TP_1") (pintype "passive"))
      (node (ref "U1") (pin "28") (pinfunction "SDA_28") (pintype "passive"))
    )
    (net (code "5") (name "/CFG0") (class "Default")
      (node (ref "R32") (pin "1") (pinfunction "1_1") (pintype "passive"))
      (node (ref "R35") (pin "2") (pinfunction "2_2") (pintype "passive"))
      (node (ref "TP34") (pin "1") (pinfunction "TP_1") (pintype "passive"))
      (node (ref "U1") (pin "4") (pinfunction "CFG0_4") (pintype "input"))
    )
    (net (code "6") (name "/CKA_N") (class "Default")
      (node (ref "C69") (pin "2") (pinfunction "2_2") (pintype "passive"))
      (node (ref "U1") (pin "40") (pinfunction "CKAN_40") (pintype "bidirectional"))
    )
    (net (code "7") (name "/CKA_P") (class "Default")
      (node (ref "C68") (pin "2") (pinfunction "2_2") (pintype "passive"))
      (node (ref "U1") (pin "39") (pinfunction "CKAP_39") (pintype "bidirectional"))
    )
    (net (code "8") (name "/CKB_N") (class "Default")
      (node (ref "C41") (pin "1") (pinfunction "1_1") (pintype "passive"))
      (node (ref "U1") (pin "46") (pinfunction "NC/CKBN_46") (pintype "passive"))
    )
    (net (code "9") (name "/CKB_P") (class "Default")
      (node (ref "C38") (pin "1") (pinfunction "1_1") (pintype "passive"))
      (node (ref "U1") (pin "45") (pinfunction "NC/CKBP_45") (pintype "passive"))
    )
    (net (code "10") (name "/CKC_N") (class "Default")
      (node (ref "C27") (pin "1") (pinfunction "1_1") (pintype "passive"))
      (node (ref "U1") (pin "34") (pinfunction "CKCN_34") (pintype "bidirectional"))
    )
    (net (code "11") (name "/CKC_P") (class "Default")
      (node (ref "C24") (pin "1") (pinfunction "1_1") (pintype "passive"))
      (node (ref "U1") (pin "33") (pinfunction "CKCP_33") (pintype "bidirectional"))
    )
    (net (code "12") (name "/CKF_N") (class "Default")
      (node (ref "C71") (pin "2") (pinfunction "2_2") (pintype "passive"))
      (node (ref "U1") (pin "52") (pinfunction "NC/CKFN_52") (pintype "passive"))
    )
    (net (code "13") (name "/CKF_P") (class "Default")
      (node (ref "C70") (pin "2") (pinfunction "2_2") (pintype "passive"))
      (node (ref "U1") (pin "51") (pinfunction "NC/CKFP_51") (pintype "passive"))
    )
    (net (code "14") (name "/CSI0_CK_N") (class "Default")
      (node (ref "C27") (pin "2") (pinfunction "2_2") (pintype "passive"))
    )
    (net (code "15") (name "/CSI0_CK_P") (class "Default")
      (node (ref "C24") (pin "2") (pinfunction "2_2") (pintype "passive"))
    )
    (net (code "16") (name "/CSI0_D0_N") (class "Default")
      (node (ref "C15") (pin "2") (pinfunction "2_2") (pintype "passive"))
    )
    (net (code "17") (name "/CSI0_D0_P") (class "Default")
      (node (ref "C14") (pin "2") (pinfunction "2_2") (pintype "passive"))
    )
    (net (code "18") (name "/CSI0_D1_N") (class "Default")
      (node (ref "C17") (pin "2") (pinfunction "2_2") (pintype "passive"))
    )
    (net (code "19") (name "/CSI0_D1_P") (class "Default")
      (node (ref "C16") (pin "2") (pinfunction "2_2") (pintype "passive"))
    )
    (net (code "20") (name "/CSI0_D2_N") (class "Default")
      (node (ref "C19") (pin "2") (pinfunction "2_2") (pintype "passive"))
    )
    (net (code "21") (name "/CSI0_D2_P") (class "Default")
      (node (ref "C18") (pin "2") (pinfunction "2_2") (pintype "passive"))
    )
    (net (code "22") (name "/CSI0_D3_N") (class "Default")
      (node (ref "C23") (pin "2") (pinfunction "2_2") (pintype "passive"))
    )
    (net (code "23") (name "/CSI0_D3_P") (class "Default")
      (node (ref "C22") (pin "2") (pinfunction "2_2") (pintype "passive"))
    )
    (net (code "24") (name "/CSI1_CK_N") (class "Default")
      (node (ref "C41") (pin "2") (pinfunction "2_2") (pintype "passive"))
    )
    (net (code "25") (name "/CSI1_CK_P") (class "Default")
      (node (ref "C38") (pin "2") (pinfunction "2_2") (pintype "passive"))
    )
    (net (code "26") (name "/CSI1_D0_N") (class "Default")
      (node (ref "C29") (pin "2") (pinfunction "2_2") (pintype "passive"))
    )
    (net (code "27") (name "/CSI1_D0_P") (class "Default")
      (node (ref "C28") (pin "2") (pinfunction "2_2") (pintype "passive"))
    )
    (net (code "28") (name "/CSI1_D1_N") (class "Default")
      (node (ref "C31") (pin "2") (pinfunction "2_2") (pintype "passive"))
    )
    (net (code "29") (name "/CSI1_D1_P") (class "Default")
      (node (ref "C30") (pin "2") (pinfunction "2_2") (pintype "passive"))
    )
    (net (code "30") (name "/CSI1_D2_N") (class "Default")
      (node (ref "C33") (pin "2") (pinfunction "2_2") (pintype "passive"))
    )
    (net (code "31") (name "/CSI1_D2_P") (class "Default")
      (node (ref "C32") (pin "2") (pinfunction "2_2") (pintype "passive"))
    )
    (net (code "32") (name "/CSI1_D3_N") (class "Default")
      (node (ref "C37") (pin "2") (pinfunction "2_2") (pintype "passive"))
    )
    (net (code "33") (name "/CSI1_D3_P") (class "Default")
      (node (ref "C36") (pin "2") (pinfunction "2_2") (pintype "passive"))
    )
    (net (code "34") (name "/DA0_N") (class "Default")
      (node (ref "C15") (pin "1") (pinfunction "1_1") (pintype "passive"))
      (node (ref "U1") (pin "32") (pinfunction "DA0N_32") (pintype "bidirectional"))
    )
    (net (code "35") (name "/DA0_P") (class "Default")
      (node (ref "C14") (pin "1") (pinfunction "1_1") (pintype "passive"))
      (node (ref "U1") (pin "31") (pinfunction "DA0P_31") (pintype "bidirectional"))
    )
    (net (code "36") (name "/DA1_N") (class "Default")
      (node (ref "C17") (pin "1") (pinfunction "1_1") (pintype "passive"))
      (node (ref "U1") (pin "36") (pinfunction "DA1N_36") (pintype "bidirectional"))
    )
    (net (code "37") (name "/DA1_P") (class "Default")
      (node (ref "C16") (pin "1") (pinfunction "1_1") (pintype "passive"))
      (node (ref "U1") (pin "35") (pinfunction "DA1P_35") (pintype "bidirectional"))
    )
    (net (code "38") (name "/DA2_N") (class "Default")
      (node (ref "C19") (pin "1") (pinfunction "1_1") (pintype "passive"))
      (node (ref "U1") (pin "38") (pinfunction "DA2N_38") (pintype "bidirectional"))
    )
    (net (code "39") (name "/DA2_P") (class "Default")
      (node (ref "C18") (pin "1") (pinfunction "1_1") (pintype "passive"))
      (node (ref "U1") (pin "37") (pinfunction "DA2P_37") (pintype "bidirectional"))
    )
    (net (code "40") (name "/DA3_N") (class "Default")
      (node (ref "C23") (pin "1") (pinfunction "1_1") (pintype "passive"))
      (node (ref "U1") (pin "42") (pinfunction "DA3N_42") (pintype "bidirectional"))
    )
    (net (code "41") (name "/DA3_P") (class "Default")
      (node (ref "C22") (pin "1") (pinfunction "1_1") (pintype "passive"))
      (node (ref "U1") (pin "41") (pinfunction "DA3P_41") (pintype "bidirectional"))
    )
    (net (code "42") (name "/DB0_N") (class "Default")
      (node (ref "C29") (pin "1") (pinfunction "1_1") (pintype "passive"))
      (node (ref "U1") (pin "44") (pinfunction "NC/DB0N_44") (pintype "passive"))
    )
    (net (code "43") (name "/DB0_P") (class "Default")
      (node (ref "C28") (pin "1") (pinfunction "1_1") (pintype "passive"))
      (node (ref "U1") (pin "43") (pinfunction "NC/DB0P_43") (pintype "passive"))
    )
    (net (code "44") (name "/DB1_N") (class "Default")
      (node (ref "C31") (pin "1") (pinfunction "1_1") (pintype "passive"))
      (node (ref "U1") (pin "48") (pinfunction "NC/DB1N_48") (pintype "passive"))
    )
    (net (code "45") (name "/DB1_P") (class "Default")
      (node (ref "C30") (pin "1") (pinfunction "1_1") (pintype "passive"))
      (node (ref "U1") (pin "47") (pinfunction "NC/DB1P_47") (pintype "passive"))
    )
    (net (code "46") (name "/DB2_N") (class "Default")
      (node (ref "C33") (pin "1") (pinfunction "1_1") (pintype "passive"))
      (node (ref "U1") (pin "50") (pinfunction "NC/DB2N_50") (pintype "passive"))
    )
    (net (code "47") (name "/DB2_P") (class "Default")
      (node (ref "C32") (pin "1") (pinfunction "1_1") (pintype "passive"))
      (node (ref "U1") (pin "49") (pinfunction "NC/DB2P_49") (pintype "passive"))
    )
    (net (code "48") (name "/DB3_N") (class "Default")
      (node (ref "C37") (pin "1") (pinfunction "1_1") (pintype "passive"))
      (node (ref "U1") (pin "54") (pinfunction "NC/DB3N_54") (pintype "passive"))
    )
    (net (code "49") (name "/DB3_P") (class "Default")
      (node (ref "C36") (pin "1") (pinfunction "1_1") (pintype "passive"))
      (node (ref "U1") (pin "53") (pinfunction "NC/DB3P_53") (pintype "passive"))
    )
    (net (code "50") (name "/MFP0") (class "Default")
      (node (ref "TP26") (pin "1") (pinfunction "TP_1") (pintype "passive"))
      (node (ref "U1") (pin "1") (pinfunction "MFP0_1") (pintype "bidirectional"))
    )
    (net (code "51") (name "/MFP1") (class "Default")
      (node (ref "TP28") (pin "1") (pinfunction "TP_1") (pintype "passive"))
      (node (ref "U1") (pin "2") (pinfunction "MFP1_2") (pintype "bidirectional"))
    )
    (net (code "52") (name "/MFP2") (class "Default")
      (node (ref "TP30") (pin "1") (pinfunction "TP_1") (pintype "passive"))
      (node (ref "U1") (pin "3") (pinfunction "MFP2_3") (pintype "bidirectional"))
    )
    (net (code "53") (name "/MFP3") (class "Default")
      (node (ref "TP23") (pin "1") (pinfunction "TP_1") (pintype "passive"))
      (node (ref "U1") (pin "12") (pinfunction "MFP3_12") (pintype "bidirectional"))
    )
    (net (code "54") (name "/MFP4") (class "Default")
      (node (ref "TP25") (pin "1") (pinfunction "TP_1") (pintype "passive"))
      (node (ref "U1") (pin "13") (pinfunction "MFP4_13") (pintype "bidirectional"))
    )
    (net (code "55") (name "/MFP5") (class "Default")
      (node (ref "TP27") (pin "1") (pinfunction "TP_1") (pintype "passive"))
      (node (ref "U1") (pin "14") (pinfunction "MFP5_14") (pintype "bidirectional"))
    )
    (net (code "56") (name "/MFP6") (class "Default")
      (node (ref "R31") (pin "1") (pinfunction "1_1") (pintype "passive"))
      (node (ref "R34") (pin "2") (pinfunction "2_2") (pintype "passive"))
      (node (ref "TP29") (pin "1") (pinfunction "TP_1") (pintype "passive"))
      (node (ref "U1") (pin "25") (pinfunction "CFG1/MFP6_25") (pintype "bidirectional"))
    )
    (net (code "57") (name "/MFP7") (class "Default")
      (node (ref "TP31") (pin "1") (pinfunction "TP_1") (pintype "passive"))
      (node (ref "U1") (pin "26") (pinfunction "SDA1/MFP7_26") (pintype "bidirectional"))
    )
    (net (code "58") (name "/MFP8") (class "Default")
      (node (ref "TP33") (pin "1") (pinfunction "TP_1") (pintype "passive"))
      (node (ref "U1") (pin "27") (pinfunction "SCL1/MFP8_27") (pintype "bidirectional"))
    )
    (net (code "59") (name "/PoC_A") (class "Default")
      (node (ref "C20") (pin "2") (pinfunction "2_2") (pintype "passive"))
      (node (ref "D1") (pin "1") (pinfunction "IO1_1") (pintype "bidirectional"))
      (node (ref "D1") (pin "10") (pinfunction "NC_10") (pintype "passive"))
      (node (ref "J8") (pin "2") (pinfunction "2_2") (pintype "passive"))
      (node (ref "L2") (pin "2") (pinfunction "2_2") (pintype "passive"))
    )
    (net (code "60") (name "/PoC_B") (class "Default")
      (node (ref "C21") (pin "2") (pinfunction "2_2") (pintype "passive"))
      (node (ref "D2") (pin "5") (pinfunction "IO4_5") (pintype "bidirectional"))
      (node (ref "D2") (pin "6") (pinfunction "NC_6") (pintype "passive"))
      (node (ref "J8") (pin "1") (pinfunction "1_1") (pintype "passive"))
      (node (ref "L4") (pin "2") (pinfunction "2_2") (pintype "passive"))
    )
    (net (code "61") (name "/PoC_C") (class "Default")
      (node (ref "C34") (pin "2") (pinfunction "2_2") (pintype "passive"))
      (node (ref "D3") (pin "1") (pinfunction "IO1_1") (pintype "bidirectional"))
      (node (ref "D3") (pin "10") (pinfunction "NC_10") (pintype "passive"))
      (node (ref "J8") (pin "4") (pinfunction "4_4") (pintype "passive"))
      (node (ref "L6") (pin "2") (pinfunction "2_2") (pintype "passive"))
    )
    (net (code "62") (name "/PoC_D") (class "Default")
      (node (ref "C35") (pin "2") (pinfunction "2_2") (pintype "passive"))
      (node (ref "D4") (pin "5") (pinfunction "IO4_5") (pintype "bidirectional"))
      (node (ref "D4") (pin "6") (pinfunction "NC_6") (pintype "passive"))
      (node (ref "J8") (pin "3") (pinfunction "3_3") (pintype "passive"))
      (node (ref "L8") (pin "2") (pinfunction "2_2") (pintype "passive"))
    )
    (net (code "63") (name "/PoC_PWR") (class "Default")
      (node (ref "F2") (pin "1") (pinfunction "1_1") (pintype "passive"))
      (node (ref "F3") (pin "1") (pinfunction "1_1") (pintype "passive"))
      (node (ref "F4") (pin "1") (pinfunction "1_1") (pintype "passive"))
      (node (ref "F5") (pin "1") (pinfunction "1_1") (pintype "passive"))
    )
    (net (code "64") (name "/SIOA_N") (class "Default")
      (node (ref "C25") (pin "1") (pinfunction "1_1") (pintype "passive"))
      (node (ref "U1") (pin "22") (pinfunction "SIOAN_22") (pintype "bidirectional"))
    )
    (net (code "65") (name "/SIOA_P") (class "Default")
      (node (ref "C20") (pin "1") (pinfunction "1_1") (pintype "passive"))
      (node (ref "U1") (pin "23") (pinfunction "SIOAP_23") (pintype "bidirectional"))
    )
    (net (code "66") (name "/SIOB_N") (class "Default")
      (node (ref "C26") (pin "1") (pinfunction "1_1") (pintype "passive"))
      (node (ref "U1") (pin "19") (pinfunction "SIOBN_19") (pintype "bidirectional"))
    )
    (net (code "67") (name "/SIOB_P") (class "Default")
      (node (ref "C21") (pin "1") (pinfunction "1_1") (pintype "passive"))
      (node (ref "U1") (pin "18") (pinfunction "SIOBP_18") (pintype "bidirectional"))
    )
    (net (code "68") (name "/SIOC_N") (class "Default")
      (node (ref "C39") (pin "1") (pinfunction "1_1") (pintype "passive"))
      (node (ref "U1") (pin "9") (pinfunction "SIOCN_9") (pintype "bidirectional"))
    )
    (net (code "69") (name "/SIOC_P") (class "Default")
      (node (ref "C34") (pin "1") (pinfunction "1_1") (pintype "passive"))
      (node (ref "U1") (pin "10") (pinfunction "SIOCP_10") (pintype "bidirectional"))
    )
    (net (code "70") (name "/SIOD_N") (class "Default")
      (node (ref "C40") (pin "1") (pinfunction "1_1") (pintype "passive"))
      (node (ref "U1") (pin "6") (pinfunction "SIODN_6") (pintype "bidirectional"))
    )
    (net (code "71") (name "/SIOD_P") (class "Default")
      (node (ref "C35") (pin "1") (pinfunction "1_1") (pintype "passive"))
      (node (ref "U1") (pin "5") (pinfunction "SIODP_5") (pintype "bidirectional"))
    )
    (net (code "72") (name "/X25_N") (class "Default")
      (node (ref "C43") (pin "2") (pinfunction "2_2") (pintype "passive"))
      (node (ref "U1") (pin "16") (pinfunction "X2_16") (pintype "passive"))
      (node (ref "Y1") (pin "3") (pinfunction "3_3") (pintype "passive"))
    )
    (net (code "73") (name "/X25_P") (class "Default")
      (node (ref "C42") (pin "2") (pinfunction "2_2") (pintype "passive"))
      (node (ref "U1") (pin "15") (pinfunction "X1/OSC_15") (pintype "passive"))
      (node (ref "Y1") (pin "1") (pinfunction "1_1") (pintype "passive"))
    )
    (net (code "74") (name "/XRES") (class "Default")
      (node (ref "R27") (pin "2") (pinfunction "2_2") (pintype "passive"))
      (node (ref "U1") (pin "17") (pinfunction "XRES_17") (pintype "passive"))
    )
    (net (code "75") (name "/nPWDN") (class "Default")
      (node (ref "R28") (pin "1") (pinfunction "1_1") (pintype "passive"))
      (node (ref "TP32") (pin "1") (pinfunction "TP_1") (pintype "passive"))
      (node (ref "U1") (pin "11") (pinfunction "PWDNB_11") (pintype "input"))
    )
    (net (code "76") (name "3V3_AUX") (class "Default")
      (node (ref "R25") (pin "2") (pinfunction "2_2") (pintype "passive"))
      (node (ref "R26") (pin "2") (pinfunction "2_2") (pintype "passive"))
      (node (ref "R28") (pin "2") (pinfunction "2_2") (pintype "passive"))
      (node (ref "R31") (pin "2") (pinfunction "2_2") (pintype "passive"))
      (node (ref "R32") (pin "2") (pinfunction "2_2") (pintype "passive"))
      (node (ref "R42") (pin "1") (pinfunction "1_1") (pintype "passive"))
    )
    (net (code "77") (name "GND") (class "Default")
      (node (ref "C42") (pin "1") (pinfunction "1_1") (pintype "passive"))
      (node (ref "C43") (pin "1") (pinfunction "1_1") (pintype "passive"))
      (node (ref "C44") (pin "1") (pinfunction "1_1") (pintype "passive"))
      (node (ref "C45") (pin "2") (pinfunction "2_2") (pintype "passive"))
      (node (ref "C46") (pin "1") (pinfunction "1_1") (pintype "passive"))
      (node (ref "C47") (pin "1") (pinfunction "1_1") (pintype "passive"))
      (node (ref "C48") (pin "1") (pinfunction "1_1") (pintype "passive"))
      (node (ref "C49") (pin "1") (pinfunction "1_1") (pintype "passive"))
      (node (ref "C50") (pin "1") (pinfunction "1_1") (pintype "passive"))
      (node (ref "C51") (pin "1") (pinfunction "1_1") (pintype "passive"))
      (node (ref "C52") (pin "1") (pinfunction "1_1") (pintype "passive"))
      (node (ref "C53") (pin "1") (pinfunction "1_1") (pintype "passive"))
      (node (ref "C54") (pin "1") (pinfunction "1_1") (pintype "passive"))
      (node (ref "C55") (pin "1") (pinfunction "1_1") (pintype "passive"))
      (node (ref "C56") (pin "1") (pinfunction "1_1") (pintype "passive"))
      (node (ref "C57") (pin "1") (pinfunction "1_1") (pintype "passive"))
      (node (ref "C58") (pin "1") (pinfunction "1_1") (pintype "passive"))
      (node (ref "C59") (pin "2") (pinfunction "2_2") (pintype "passive"))
      (node (ref "C60") (pin "1") (pinfunction "1_1") (pintype "passive"))
      (node (ref "C61") (pin "1") (pinfunction "1_1") (pintype "passive"))
      (node (ref "C62") (pin "1") (pinfunction "1_1") (pintype "passive"))
      (node (ref "C63") (pin "1") (pinfunction "1_1") (pintype "passive"))
      (node (ref "C64") (pin "2") (pinfunction "2_2") (pintype "passive"))
      (node (ref "C65") (pin "2") (pinfunction "2_2") (pintype "passive"))
      (node (ref "C66") (pin "2") (pinfunction "2_2") (pintype "passive"))
      (node (ref "C67") (pin "2") (pinfunction "2_2") (pintype "passive"))
      (node (ref "D1") (pin "3") (pinfunction "GND_3") (pintype "power_in"))
      (node (ref "D1") (pin "8") (pinfunction "GND_8") (pintype "power_in"))
      (node (ref "D2") (pin "3") (pinfunction "GND_3") (pintype "power_in"))
      (node (ref "D2") (pin "8") (pinfunction "GND_8") (pintype "power_in"))
      (node (ref "D3") (pin "3") (pinfunction "GND_3") (pintype "power_in"))
      (node (ref "D3") (pin "8") (pinfunction "GND_8") (pintype "power_in"))
      (node (ref "D4") (pin "3") (pinfunction "GND_3") (pintype "power_in"))
      (node (ref "D4") (pin "8") (pinfunction "GND_8") (pintype "power_in"))
      (node (ref "J8") (pin "MH1") (pinfunction "MH1_MH1") (pintype "passive"))
      (node (ref "J8") (pin "MH2") (pinfunction "MH2_MH2") (pintype "passive"))
      (node (ref "J8") (pin "MH3") (pinfunction "MH3_MH3") (pintype "passive"))
      (node (ref "J8") (pin "MH4") (pinfunction "MH4_MH4") (pintype "passive"))
      (node (ref "J8") (pin "MH5") (pinfunction "MH5_MH5") (pintype "passive"))
      (node (ref "R27") (pin "1") (pinfunction "1_1") (pintype "passive"))
      (node (ref "R29") (pin "1") (pinfunction "1_1") (pintype "passive"))
      (node (ref "R30") (pin "1") (pinfunction "1_1") (pintype "passive"))
      (node (ref "R34") (pin "1") (pinfunction "1_1") (pintype "passive"))
      (node (ref "R35") (pin "1") (pinfunction "1_1") (pintype "passive"))
      (node (ref "R36") (pin "1") (pinfunction "1_1") (pintype "passive"))
      (node (ref "R37") (pin "1") (pinfunction "1_1") (pintype "passive"))
      (node (ref "U1") (pin "57") (pinfunction "GND_(EP)_57") (pintype "power_in"))
      (node (ref "U2") (pin "1") (pinfunction "GND_1") (pintype "power_in"))
      (node (ref "U3") (pin "1") (pinfunction "GND_1") (pintype "power_in"))
      (node (ref "Y1") (pin "2") (pinfunction "GND_2") (pintype "power_in"))
      (node (ref "Y1") (pin "4") (pinfunction "GND_4") (pintype "power_in"))
    )
    (net (code "78") (name "LO_VCC") (class "Default")
      (node (ref "C44") (pin "2") (pinfunction "2_2") (pintype "passive"))
      (node (ref "C58") (pin "2") (pinfunction "2_2") (pintype "passive"))
      (node (ref "U2") (pin "3") (pinfunction "VIN_3") (pintype "power_in"))
      (node (ref "U3") (pin "3") (pinfunction "VIN_3") (pintype "power_in"))
    )
    (net (code "79") (name "Net-(C25-Pad2)") (class "Default")
      (node (ref "C25") (pin "2") (pinfunction "2_2") (pintype "passive"))
      (node (ref "R29") (pin "2") (pinfunction "2_2") (pintype "passive"))
    )
    (net (code "80") (name "Net-(C26-Pad2)") (class "Default")
      (node (ref "C26") (pin "2") (pinfunction "2_2") (pintype "passive"))
      (node (ref "R30") (pin "2") (pinfunction "2_2") (pintype "passive"))
    )
    (net (code "81") (name "Net-(C39-Pad2)") (class "Default")
      (node (ref "C39") (pin "2") (pinfunction "2_2") (pintype "passive"))
      (node (ref "R36") (pin "2") (pinfunction "2_2") (pintype "passive"))
    )
    (net (code "82") (name "Net-(C40-Pad2)") (class "Default")
      (node (ref "C40") (pin "2") (pinfunction "2_2") (pintype "passive"))
      (node (ref "R37") (pin "2") (pinfunction "2_2") (pintype "passive"))
    )
    (net (code "83") (name "Net-(C46-Pad2)") (class "Default")
      (node (ref "C46") (pin "2") (pinfunction "2_2") (pintype "passive"))
      (node (ref "C47") (pin "2") (pinfunction "2_2") (pintype "passive"))
      (node (ref "U1") (pin "8") (pinfunction "CAP_VDD_8") (pintype "power_in"))
    )
    (net (code "84") (name "Net-(C48-Pad2)") (class "Default")
      (node (ref "C48") (pin "2") (pinfunction "2_2") (pintype "passive"))
      (node (ref "C49") (pin "2") (pinfunction "2_2") (pintype "passive"))
      (node (ref "U1") (pin "20") (pinfunction "CAP_VDD_20") (pintype "power_in"))
    )
    (net (code "85") (name "Net-(C50-Pad2)") (class "Default")
      (node (ref "C50") (pin "2") (pinfunction "2_2") (pintype "passive"))
      (node (ref "C51") (pin "2") (pinfunction "2_2") (pintype "passive"))
      (node (ref "R38") (pin "2") (pinfunction "2_2") (pintype "passive"))
      (node (ref "U1") (pin "55") (pinfunction "VDD_55") (pintype "power_in"))
    )
    (net (code "86") (name "Net-(C52-Pad2)") (class "Default")
      (node (ref "C52") (pin "2") (pinfunction "2_2") (pintype "passive"))
      (node (ref "C53") (pin "2") (pinfunction "2_2") (pintype "passive"))
      (node (ref "R39") (pin "2") (pinfunction "2_2") (pintype "passive"))
      (node (ref "U1") (pin "56") (pinfunction "VDD_56") (pintype "power_in"))
    )
    (net (code "87") (name "Net-(C54-Pad2)") (class "Default")
      (node (ref "C54") (pin "2") (pinfunction "2_2") (pintype "passive"))
      (node (ref "C55") (pin "2") (pinfunction "2_2") (pintype "passive"))
      (node (ref "R40") (pin "2") (pinfunction "2_2") (pintype "passive"))
      (node (ref "U1") (pin "7") (pinfunction "VDD18_7") (pintype "power_in"))
    )
    (net (code "88") (name "Net-(C56-Pad2)") (class "Default")
      (node (ref "C56") (pin "2") (pinfunction "2_2") (pintype "passive"))
      (node (ref "C57") (pin "2") (pinfunction "2_2") (pintype "passive"))
      (node (ref "R41") (pin "2") (pinfunction "2_2") (pintype "passive"))
      (node (ref "U1") (pin "21") (pinfunction "VDD18_21") (pintype "power_in"))
    )
    (net (code "89") (name "Net-(C64-Pad1)") (class "Default")
      (node (ref "C64") (pin "1") (pinfunction "1_1") (pintype "passive"))
      (node (ref "F2") (pin "2") (pinfunction "2_2") (pintype "passive"))
      (node (ref "L1") (pin "1") (pinfunction "1_1") (pintype "passive"))
      (node (ref "R44") (pin "1") (pinfunction "1_1") (pintype "passive"))
    )
    (net (code "90") (name "Net-(C65-Pad1)") (class "Default")
      (node (ref "C65") (pin "1") (pinfunction "1_1") (pintype "passive"))
      (node (ref "F3") (pin "2") (pinfunction "2_2") (pintype "passive"))
      (node (ref "L3") (pin "1") (pinfunction "1_1") (pintype "passive"))
      (node (ref "R45") (pin "1") (pinfunction "1_1") (pintype "passive"))
    )
    (net (code "91") (name "Net-(C66-Pad1)") (class "Default")
      (node (ref "C66") (pin "1") (pinfunction "1_1") (pintype "passive"))
      (node (ref "F4") (pin "2") (pinfunction "2_2") (pintype "passive"))
      (node (ref "L5") (pin "1") (pinfunction "1_1") (pintype "passive"))
      (node (ref "R46") (pin "1") (pinfunction "1_1") (pintype "passive"))
    )
    (net (code "92") (name "Net-(C67-Pad1)") (class "Default")
      (node (ref "C67") (pin "1") (pinfunction "1_1") (pintype "passive"))
      (node (ref "F5") (pin "2") (pinfunction "2_2") (pintype "passive"))
      (node (ref "L7") (pin "1") (pinfunction "1_1") (pintype "passive"))
      (node (ref "R47") (pin "1") (pinfunction "1_1") (pintype "passive"))
    )
    (net (code "93") (name "Net-(L1-Pad2)") (class "Default")
      (node (ref "L1") (pin "2") (pinfunction "2_2") (pintype "passive"))
      (node (ref "L2") (pin "1") (pinfunction "1_1") (pintype "passive"))
      (node (ref "R44") (pin "2") (pinfunction "2_2") (pintype "passive"))
    )
    (net (code "94") (name "Net-(L3-Pad2)") (class "Default")
      (node (ref "L3") (pin "2") (pinfunction "2_2") (pintype "passive"))
      (node (ref "L4") (pin "1") (pinfunction "1_1") (pintype "passive"))
      (node (ref "R45") (pin "2") (pinfunction "2_2") (pintype "passive"))
    )
    (net (code "95") (name "Net-(L5-Pad2)") (class "Default")
      (node (ref "L5") (pin "2") (pinfunction "2_2") (pintype "passive"))
      (node (ref "L6") (pin "1") (pinfunction "1_1") (pintype "passive"))
      (node (ref "R46") (pin "2") (pinfunction "2_2") (pintype "passive"))
    )
    (net (code "96") (name "Net-(L7-Pad2)") (class "Default")
      (node (ref "L7") (pin "2") (pinfunction "2_2") (pintype "passive"))
      (node (ref "L8") (pin "1") (pinfunction "1_1") (pintype "passive"))
      (node (ref "R47") (pin "2") (pinfunction "2_2") (pintype "passive"))
    )
    (net (code "97") (name "Net-(TP18-TP)") (class "Default")
      (node (ref "C68") (pin "1") (pinfunction "1_1") (pintype "passive"))
      (node (ref "TP18") (pin "1") (pinfunction "TP_1") (pintype "passive"))
    )
    (net (code "98") (name "Net-(TP19-TP)") (class "Default")
      (node (ref "C69") (pin "1") (pinfunction "1_1") (pintype "passive"))
      (node (ref "TP19") (pin "1") (pinfunction "TP_1") (pintype "passive"))
    )
    (net (code "99") (name "Net-(TP20-TP)") (class "Default")
      (node (ref "C70") (pin "1") (pinfunction "1_1") (pintype "passive"))
      (node (ref "TP20") (pin "1") (pinfunction "TP_1") (pintype "passive"))
    )
    (net (code "100") (name "Net-(TP21-TP)") (class "Default")
      (node (ref "C71") (pin "1") (pinfunction "1_1") (pintype "passive"))
      (node (ref "TP21") (pin "1") (pinfunction "TP_1") (pintype "passive"))
    )
    (net (code "101") (name "Net-(U1B-VDDIO)") (class "Default")
      (node (ref "C60") (pin "2") (pinfunction "2_2") (pintype "passive"))
      (node (ref "C61") (pin "2") (pinfunction "2_2") (pintype "passive"))
      (node (ref "R42") (pin "2") (pinfunction "2_2") (pintype "passive"))
      (node (ref "U1") (pin "24") (pinfunction "VDDIO_24") (pintype "power_in"))
    )
    (net (code "102") (name "Net-(U1B-VTERM)") (class "Default")
      (node (ref "C62") (pin "2") (pinfunction "2_2") (pintype "passive"))
      (node (ref "C63") (pin "2") (pinfunction "2_2") (pintype "passive"))
      (node (ref "R43") (pin "2") (pinfunction "2_2") (pintype "passive"))
      (node (ref "U1") (pin "30") (pinfunction "VTERM_30") (pintype "power_in"))
    )
    (net (code "103") (name "unconnected-(D1-IO2-Pad2)") (class "Default")
      (node (ref "D1") (pin "2") (pinfunction "IO2_2") (pintype "bidirectional"))
    )
    (net (code "104") (name "unconnected-(D1-IO3-Pad4)") (class "Default")
      (node (ref "D1") (pin "4") (pinfunction "IO3_4") (pintype "bidirectional"))
    )
    (net (code "105") (name "unconnected-(D1-IO4-Pad5)") (class "Default")
      (node (ref "D1") (pin "5") (pinfunction "IO4_5") (pintype "bidirectional"))
    )
    (net (code "106") (name "unconnected-(D1-NC-Pad6)") (class "Default")
      (node (ref "D1") (pin "6") (pinfunction "NC_6") (pintype "passive"))
    )
    (net (code "107") (name "unconnected-(D1-NC-Pad7)") (class "Default")
      (node (ref "D1") (pin "7") (pinfunction "NC_7") (pintype "passive"))
    )
    (net (code "108") (name "unconnected-(D1-NC-Pad9)") (class "Default")
      (node (ref "D1") (pin "9") (pinfunction "NC_9") (pintype "passive"))
    )
    (net (code "109") (name "unconnected-(D2-IO1-Pad1)") (class "Default")
      (node (ref "D2") (pin "1") (pinfunction "IO1_1") (pintype "bidirectional"))
    )
    (net (code "110") (name "unconnected-(D2-IO2-Pad2)") (class "Default")
      (node (ref "D2") (pin "2") (pinfunction "IO2_2") (pintype "bidirectional"))
    )
    (net (code "111") (name "unconnected-(D2-IO3-Pad4)") (class "Default")
      (node (ref "D2") (pin "4") (pinfunction "IO3_4") (pintype "bidirectional"))
    )
    (net (code "112") (name "unconnected-(D2-NC-Pad7)") (class "Default")
      (node (ref "D2") (pin "7") (pinfunction "NC_7") (pintype "passive"))
    )
    (net (code "113") (name "unconnected-(D2-NC-Pad9)") (class "Default")
      (node (ref "D2") (pin "9") (pinfunction "NC_9") (pintype "passive"))
    )
    (net (code "114") (name "unconnected-(D2-NC-Pad10)") (class "Default")
      (node (ref "D2") (pin "10") (pinfunction "NC_10") (pintype "passive"))
    )
    (net (code "115") (name "unconnected-(D3-IO2-Pad2)") (class "Default")
      (node (ref "D3") (pin "2") (pinfunction "IO2_2") (pintype "bidirectional"))
    )
    (net (code "116") (name "unconnected-(D3-IO3-Pad4)") (class "Default")
      (node (ref "D3") (pin "4") (pinfunction "IO3_4") (pintype "bidirectional"))
    )
    (net (code "117") (name "unconnected-(D3-IO4-Pad5)") (class "Default")
      (node (ref "D3") (pin "5") (pinfunction "IO4_5") (pintype "bidirectional"))
    )
    (net (code "118") (name "unconnected-(D3-NC-Pad6)") (class "Default")
      (node (ref "D3") (pin "6") (pinfunction "NC_6") (pintype "passive"))
    )
    (net (code "119") (name "unconnected-(D3-NC-Pad7)") (class "Default")
      (node (ref "D3") (pin "7") (pinfunction "NC_7") (pintype "passive"))
    )
    (net (code "120") (name "unconnected-(D3-NC-Pad9)") (class "Default")
      (node (ref "D3") (pin "9") (pinfunction "NC_9") (pintype "passive"))
    )
    (net (code "121") (name "unconnected-(D4-IO1-Pad1)") (class "Default")
      (node (ref "D4") (pin "1") (pinfunction "IO1_1") (pintype "bidirectional"))
    )
    (net (code "122") (name "unconnected-(D4-IO2-Pad2)") (class "Default")
      (node (ref "D4") (pin "2") (pinfunction "IO2_2") (pintype "bidirectional"))
    )
    (net (code "123") (name "unconnected-(D4-IO3-Pad4)") (class "Default")
      (node (ref "D4") (pin "4") (pinfunction "IO3_4") (pintype "bidirectional"))
    )
    (net (code "124") (name "unconnected-(D4-NC-Pad7)") (class "Default")
      (node (ref "D4") (pin "7") (pinfunction "NC_7") (pintype "passive"))
    )
    (net (code "125") (name "unconnected-(D4-NC-Pad9)") (class "Default")
      (node (ref "D4") (pin "9") (pinfunction "NC_9") (pintype "passive"))
    )
    (net (code "126") (name "unconnected-(D4-NC-Pad10)") (class "Default")
      (node (ref "D4") (pin "10") (pinfunction "NC_10") (pintype "passive"))
    )
  )
)
